# Conectors.net
KiCad netlist of a schematic drawn in Altium Designer
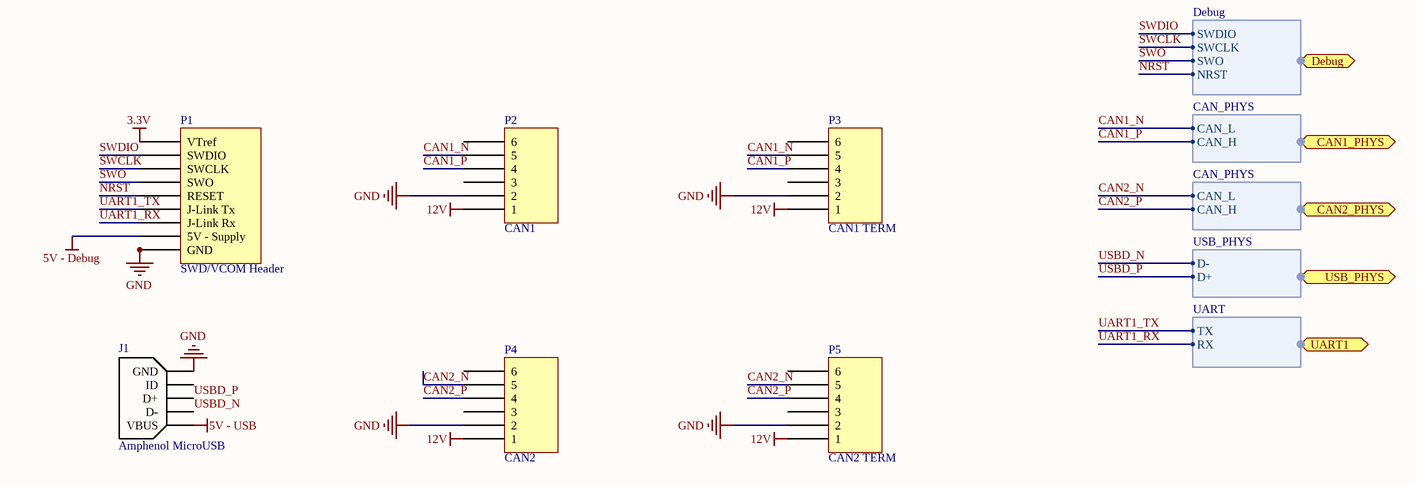
[diagram p0: Conectors.SchDoc]

(export (version "E")
  (design (tool "Eeschema 10.0.6"))
  (components
    (comp (ref "J1")
      (value "Amphenol MicroUSB")
      (footprint "Amphenol MicroUSB")
      (libsource (lib "Amphenol MicroUSB") (part "Amphenol MicroUSB - 609-4618-1-ND"))
    )
    (comp (ref "P1")
      (value "SWD/VCOM Header")
      (footprint "Samtec TST-110-01-G-D")
      (libsource (lib "SWD+VCOM Header - J-Link") (part "SWD/VCOM Header"))
    )
    (comp (ref "P2")
      (value "CAN1")
      (footprint "Molex Microfit 3.0 3x2:PCB_MLX_MICROFIT_3X2")
      (libsource (lib "Molex Microfit 3.0 3x2") (part "SCH_MLX_MICROFIT_3X2"))
    )
    (comp (ref "P3")
      (value "CAN1 TERM")
      (footprint "Molex Microfit 3.0 3x2:PCB_MLX_MICROFIT_3X2")
      (libsource (lib "Molex Microfit 3.0 3x2") (part "SCH_MLX_MICROFIT_3X2"))
    )
    (comp (ref "P4")
      (value "CAN2")
      (footprint "Molex Microfit 3.0 3x2:PCB_MLX_MICROFIT_3X2")
      (libsource (lib "Molex Microfit 3.0 3x2") (part "SCH_MLX_MICROFIT_3X2"))
    )
    (comp (ref "P5")
      (value "CAN2 TERM")
      (footprint "Molex Microfit 3.0 3x2:PCB_MLX_MICROFIT_3X2")
      (libsource (lib "Molex Microfit 3.0 3x2") (part "SCH_MLX_MICROFIT_3X2"))
    )
  )
  (nets
    (net (code "5") (name "/CAN1_N") (class "Default")
      (node (ref "P2") (pin "5") (pinfunction "5_5") (pintype "passive"))
      (node (ref "P3") (pin "5") (pinfunction "5_5") (pintype "passive"))
    )
    (net (code "6") (name "/CAN1_P") (class "Default")
      (node (ref "P2") (pin "4") (pinfunction "4_4") (pintype "passive"))
      (node (ref "P3") (pin "4") (pinfunction "4_4") (pintype "passive"))
    )
    (net (code "7") (name "/CAN2_N") (class "Default")
      (node (ref "P4") (pin "5") (pinfunction "5_5") (pintype "passive"))
      (node (ref "P5") (pin "5") (pinfunction "5_5") (pintype "passive"))
    )
    (net (code "8") (name "/CAN2_P") (class "Default")
      (node (ref "P4") (pin "4") (pinfunction "4_4") (pintype "passive"))
      (node (ref "P5") (pin "4") (pinfunction "4_4") (pintype "passive"))
    )
    (net (code "9") (name "/NRST") (class "Default")
      (node (ref "P1") (pin "15") (pinfunction "RESET_15") (pintype "passive"))
    )
    (net (code "10") (name "/SWCLK") (class "Default")
      (node (ref "P1") (pin "9") (pinfunction "SWCLK_9") (pintype "passive"))
    )
    (net (code "11") (name "/SWDIO") (class "Default")
      (node (ref "P1") (pin "7") (pinfunction "SWDIO_7") (pintype "passive"))
    )
    (net (code "12") (name "/SWO") (class "Default")
      (node (ref "P1") (pin "13") (pinfunction "SWO_13") (pintype "passive"))
    )
    (net (code "13") (name "/UART1_RX") (class "Default")
      (node (ref "P1") (pin "17") (pinfunction "J-Link_Rx_17") (pintype "passive"))
    )
    (net (code "14") (name "/UART1_TX") (class "Default")
      (node (ref "P1") (pin "5") (pinfunction "J-Link_Tx_5") (pintype "passive"))
    )
    (net (code "15") (name "/USBD_N") (class "Default")
      (node (ref "J1") (pin "2") (pinfunction "D-_2") (pintype "passive"))
    )
    (net (code "16") (name "/USBD_P") (class "Default")
      (node (ref "J1") (pin "3") (pinfunction "D+_3") (pintype "passive"))
    )
    (net (code "21") (name "3.3V") (class "Default")
      (node (ref "P1") (pin "1") (pinfunction "VTref_1") (pintype "passive"))
    )
    (net (code "22") (name "5V - Debug") (class "Default")
      (node (ref "P1") (pin "19") (pinfunction "5V_-_Supply_19") (pintype "passive"))
    )
    (net (code "23") (name "5V - USB") (class "Default")
      (node (ref "J1") (pin "1") (pinfunction "VBUS_1") (pintype "passive"))
    )
    (net (code "24") (name "12V") (class "Default")
      (node (ref "P2") (pin "1") (pinfunction "1_1") (pintype "passive"))
      (node (ref "P3") (pin "1") (pinfunction "1_1") (pintype "passive"))
      (node (ref "P4") (pin "1") (pinfunction "1_1") (pintype "passive"))
      (node (ref "P5") (pin "1") (pinfunction "1_1") (pintype "passive"))
    )
    (net (code "25") (name "GND") (class "Default")
      (node (ref "J1") (pin "5") (pinfunction "GND_5") (pintype "passive"))
      (node (ref "P1") (pin "10") (pinfunction "GND_10") (pintype "passive"))
      (node (ref "P1") (pin "12") (pinfunction "GND_12") (pintype "passive"))
      (node (ref "P1") (pin "4") (pinfunction "GND_4") (pintype "passive"))
      (node (ref "P1") (pin "6") (pinfunction "GND_6") (pintype "passive"))
      (node (ref "P1") (pin "8") (pinfunction "GND_8") (pintype "passive"))
      (node (ref "P2") (pin "2") (pinfunction "2_2") (pintype "passive"))
      (node (ref "P3") (pin "2") (pinfunction "2_2") (pintype "passive"))
      (node (ref "P4") (pin "2") (pinfunction "2_2") (pintype "passive"))
      (node (ref "P5") (pin "2") (pinfunction "2_2") (pintype "passive"))
    )
    (net (code "26") (name "unconnected-(J1-ID-Pad4)") (class "Default")
      (node (ref "J1") (pin "4") (pinfunction "ID_4") (pintype "passive"))
    )
    (net (code "27") (name "unconnected-(P2-Pad3)") (class "Default")
      (node (ref "P2") (pin "3") (pinfunction "3_3") (pintype "passive"))
    )
    (net (code "28") (name "unconnected-(P2-Pad6)") (class "Default")
      (node (ref "P2") (pin "6") (pinfunction "6_6") (pintype "passive"))
    )
    (net (code "29") (name "unconnected-(P3-Pad3)") (class "Default")
      (node (ref "P3") (pin "3") (pinfunction "3_3") (pintype "passive"))
    )
    (net (code "30") (name "unconnected-(P3-Pad6)") (class "Default")
      (node (ref "P3") (pin "6") (pinfunction "6_6") (pintype "passive"))
    )
    (net (code "31") (name "unconnected-(P4-Pad3)") (class "Default")
      (node (ref "P4") (pin "3") (pinfunction "3_3") (pintype "passive"))
    )
    (net (code "32") (name "unconnected-(P4-Pad6)") (class "Default")
      (node (ref "P4") (pin "6") (pinfunction "6_6") (pintype "passive"))
    )
    (net (code "33") (name "unconnected-(P5-Pad3)") (class "Default")
      (node (ref "P5") (pin "3") (pinfunction "3_3") (pintype "passive"))
    )
    (net (code "34") (name "unconnected-(P5-Pad6)") (class "Default")
      (node (ref "P5") (pin "6") (pinfunction "6_6") (pintype "passive"))
    )
  )
)
